# MCU.net
KiCad netlist of a schematic drawn in Altium Designer
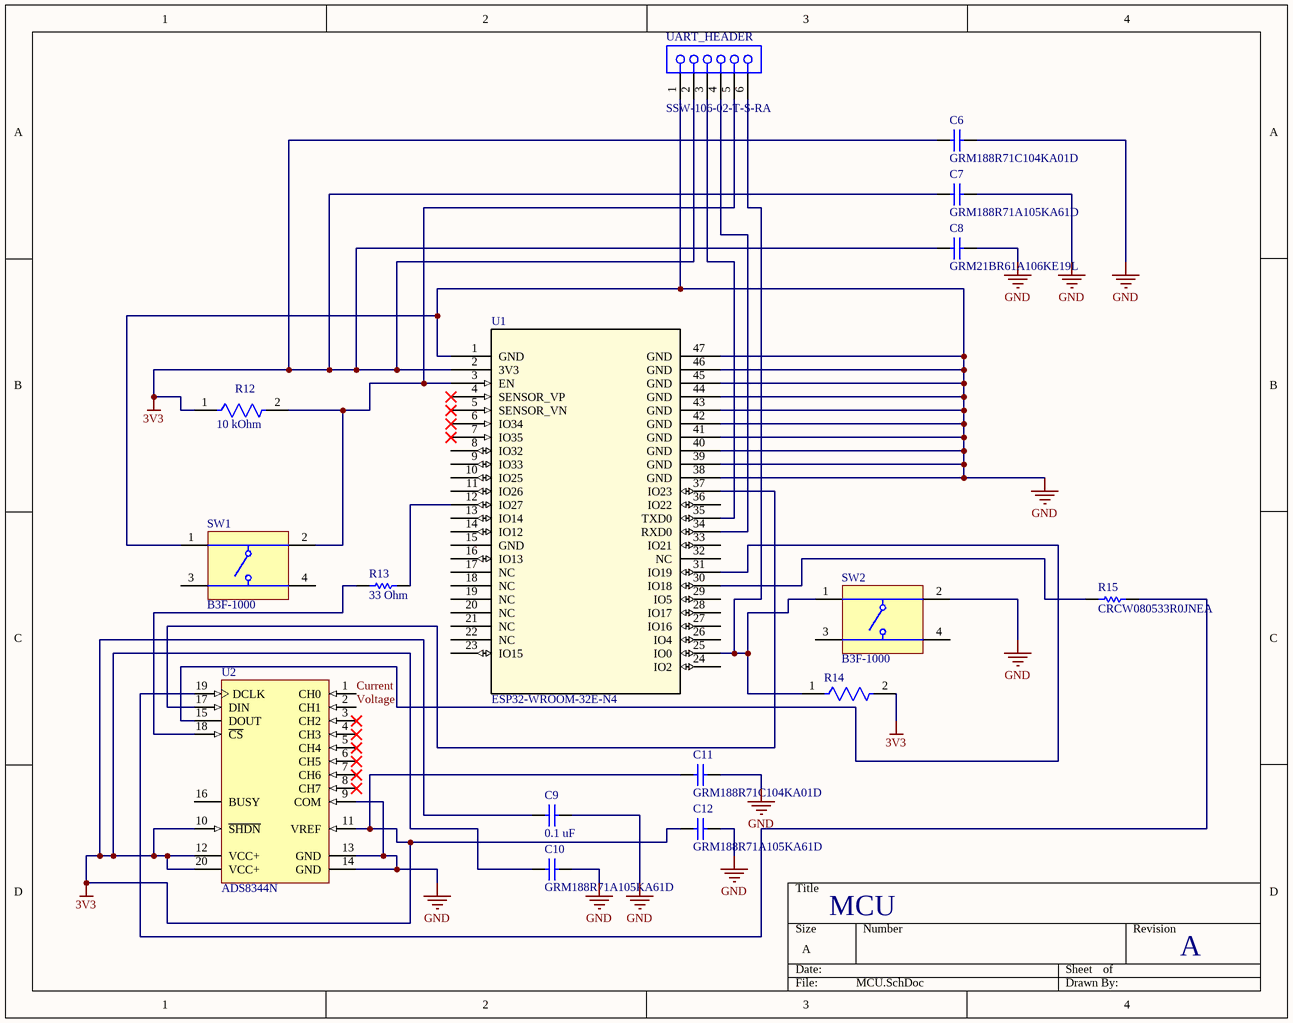
[diagram p0: MCU.SchDoc]

(export (version "E")
  (design (tool "Eeschema 10.0.6"))
  (components
    (comp (ref "C6")
      (value "GRM188R71C104KA01D")
      (footprint "MURA-0603_H_0.9_N")
      (description "CAP, Ceramic, 0.1 uF, 10%, 16 V, 0603, RoHS, Tape and Reel")
      (fields (field (name "MANUFACTURER") "Murata") (field (name "TOLERANCE") "10%"))
      (libsource (lib "Altium Content Vault") (part "CAP-NP-2"))
    )
    (comp (ref "C7")
      (value "GRM188R71A105KA61D")
      (footprint "CAPC1608X90X35ML10T15")
      (fields (field (name "MANUFACTURER") "Murata"))
      (libsource (lib "Altium Content Vault") (part "CAP"))
    )
    (comp (ref "C8")
      (value "GRM21BR61A106KE19L")
      (footprint "MURA-0805_H_1.35_L")
      (description "CAP, Ceramic, 10 uF, 10%, 10 V, 0805, RoHS, Tape and Reel")
      (fields (field (name "MANUFACTURER") "Murata") (field (name "TOLERANCE") "±10%"))
      (libsource (lib "Altium Content Vault") (part "CAP-NP-2"))
    )
    (comp (ref "C9")
      (value "0.1 uF")
      (footprint "MURA-0603_H_0.9_N")
      (description "CAP, Ceramic, 0.1 uF, 10%, 16 V, 0603, RoHS, Tape and Reel")
      (fields (field (name "MANUFACTURER") "Murata") (field (name "TOLERANCE") "10%"))
      (libsource (lib "Altium Content Vault") (part "CAP-NP-2"))
    )
    (comp (ref "C10")
      (value "GRM188R71A105KA61D")
      (footprint "CAPC1608X90X35ML10T15")
      (fields (field (name "MANUFACTURER") "Murata"))
      (libsource (lib "Altium Content Vault") (part "CAP"))
    )
    (comp (ref "C11")
      (value "GRM188R71C104KA01D")
      (footprint "MURA-0603_H_0.9_N")
      (description "CAP, Ceramic, 0.1 uF, 10%, 16 V, 0603, RoHS, Tape and Reel")
      (fields (field (name "MANUFACTURER") "Murata") (field (name "TOLERANCE") "10%"))
      (libsource (lib "Altium Content Vault") (part "CAP-NP-2"))
    )
    (comp (ref "C12")
      (value "GRM188R71A105KA61D")
      (footprint "CAPC1608X90X35ML10T15")
      (fields (field (name "MANUFACTURER") "Murata"))
      (libsource (lib "Altium Content Vault") (part "CAP"))
    )
    (comp (ref "R12")
      (value "10 kOhm")
      (footprint "FP-RC0603-0_55-IPC_B")
      (description "RES 10K OHM 1% 1/10W 0603")
      (fields (field (name "TOLERANCE") "1%"))
      (libsource (lib "Altium Content Vault") (part "1029c3af85768c4190bb7ad29bc67b5"))
    )
    (comp (ref "R13")
      (value "33 Ohm")
      (footprint "RESC2013X50X30ML20T20")
      (fields (field (name "MANUFACTURER") "Vishay Dale") (field (name "PART NUMBER") "CRCW080533R0JNEA"))
      (libsource (lib "Altium Content Vault") (part "RES"))
    )
    (comp (ref "R14")
      (value "RC0603FR-0710KL")
      (footprint "FP-RC0603-0_55-IPC_B")
      (description "RES 10K OHM 1% 1/10W 0603")
      (fields (field (name "TOLERANCE") "1%"))
      (libsource (lib "Altium Content Vault") (part "1029c3af85768c4190bb7ad29bc67b5"))
    )
    (comp (ref "R15")
      (value "CRCW080533R0JNEA")
      (footprint "RESC2013X50X30ML20T20")
      (fields (field (name "MANUFACTURER") "Vishay Dale"))
      (libsource (lib "Altium Content Vault") (part "RES"))
    )
    (comp (ref "SW1")
      (value "B3F-1000")
      (footprint "OMRON-B3F-1000-4_V")
      (description "Tactile Switch, SPST-NO, 0.05 A, 5 to 24 V, -25 to 70 degC, 4-Pin THD, RoHS, Bulk")
      (libsource (lib "Altium Content Vault") (part "SW-SPST-4_A"))
    )
    (comp (ref "SW2")
      (value "B3F-1000")
      (footprint "OMRON-B3F-1000-4_V")
      (description "Tactile Switch, SPST-NO, 0.05 A, 5 to 24 V, -25 to 70 degC, 4-Pin THD, RoHS, Bulk")
      (libsource (lib "Altium Content Vault") (part "SW-SPST-4_A"))
    )
    (comp (ref "U1")
      (value "ESP32-WROOM-32E-N4")
      (footprint "ESP32­WROOM­32E_EXP")
      (description "Description")
      (fields (field (name "COPYRIGHT") "Copyright (C) 2025 Ultra Librarian. All rights reserved."))
      (libsource (lib "ESP32-WROOM-32E-N4") (part "ESP32-WROOM-32E-N4"))
    )
    (comp (ref "U2")
      (value "ADS8344N")
      (footprint "TI-DB20_L")
      (fields (field (name "MANUFACTURER") "Texas Instruments"))
      (libsource (lib "Altium Content Vault") (part "TI-ADS8344DB_DBQ20"))
    )
    (comp (ref "UART_HEADER")
      (value "SSW-106-02-T-S-RA")
      (footprint "SMTC-SSW-106-02-X-S-RA")
      (description "SQ Post Socket, Through-hole, Right Angle, -55 to 105 degC, 2.54mm Pitch, 6-Pin, Female, RoHS")
      (fields (field (name "MANUFACTURER") "Samtec"))
      (libsource (lib "Altium Content Vault") (part "SMTC-SSW-106-02-X-S-X"))
    )
  )
  (nets
    (net (code "1") (name "/Current") (class "Default")
      (node (ref "U2") (pin "1") (pinfunction "CH0_1") (pintype "input"))
    )
    (net (code "2") (name "/Voltage") (class "Default")
      (node (ref "U2") (pin "2") (pinfunction "CH1_2") (pintype "input"))
    )
    (net (code "3") (name "3V3") (class "Default")
      (node (ref "C10") (pin "1") (pinfunction "1_1") (pintype "passive"))
      (node (ref "C11") (pin "1") (pinfunction "1_1") (pintype "passive"))
      (node (ref "C12") (pin "1") (pinfunction "1_1") (pintype "passive"))
      (node (ref "C6") (pin "1") (pinfunction "1_1") (pintype "passive"))
      (node (ref "C7") (pin "1") (pinfunction "1_1") (pintype "passive"))
      (node (ref "C8") (pin "1") (pinfunction "1_1") (pintype "passive"))
      (node (ref "C9") (pin "1") (pinfunction "1_1") (pintype "passive"))
      (node (ref "R12") (pin "1") (pinfunction "1_1") (pintype "passive"))
      (node (ref "R14") (pin "2") (pinfunction "2_2") (pintype "passive"))
      (node (ref "U1") (pin "2") (pinfunction "3V3_2") (pintype "power_in"))
      (node (ref "U2") (pin "10") (pinfunction "~{SHDN}_10") (pintype "input"))
      (node (ref "U2") (pin "11") (pinfunction "VREF_11") (pintype "input"))
      (node (ref "U2") (pin "12") (pinfunction "VCC+_12") (pintype "power_in"))
      (node (ref "U2") (pin "20") (pinfunction "VCC+_20") (pintype "power_in"))
      (node (ref "UART_HEADER") (pin "2") (pinfunction "2_2") (pintype "passive"))
    )
    (net (code "4") (name "GND") (class "Default")
      (node (ref "C10") (pin "2") (pinfunction "2_2") (pintype "passive"))
      (node (ref "C11") (pin "2") (pinfunction "2_2") (pintype "passive"))
      (node (ref "C12") (pin "2") (pinfunction "2_2") (pintype "passive"))
      (node (ref "C6") (pin "2") (pinfunction "2_2") (pintype "passive"))
      (node (ref "C7") (pin "2") (pinfunction "2_2") (pintype "passive"))
      (node (ref "C8") (pin "2") (pinfunction "2_2") (pintype "passive"))
      (node (ref "C9") (pin "2") (pinfunction "2_2") (pintype "passive"))
      (node (ref "SW1") (pin "1") (pinfunction "1_1") (pintype "passive"))
      (node (ref "SW2") (pin "2") (pinfunction "2_2") (pintype "passive"))
      (node (ref "U1") (pin "1") (pinfunction "GND_1") (pintype "power_in"))
      (node (ref "U1") (pin "38") (pinfunction "GND_38") (pintype "power_in"))
      (node (ref "U1") (pin "39") (pinfunction "GND_39") (pintype "power_in"))
      (node (ref "U1") (pin "40") (pinfunction "GND_40") (pintype "power_in"))
      (node (ref "U1") (pin "41") (pinfunction "GND_41") (pintype "power_in"))
      (node (ref "U1") (pin "42") (pinfunction "GND_42") (pintype "power_in"))
      (node (ref "U1") (pin "43") (pinfunction "GND_43") (pintype "power_in"))
      (node (ref "U1") (pin "44") (pinfunction "GND_44") (pintype "power_in"))
      (node (ref "U1") (pin "45") (pinfunction "GND_45") (pintype "power_in"))
      (node (ref "U1") (pin "46") (pinfunction "GND_46") (pintype "power_in"))
      (node (ref "U1") (pin "47") (pinfunction "GND_47") (pintype "power_in"))
      (node (ref "U2") (pin "13") (pinfunction "GND_13") (pintype "power_in"))
      (node (ref "U2") (pin "14") (pinfunction "GND_14") (pintype "power_in"))
      (node (ref "U2") (pin "9") (pinfunction "COM_9") (pintype "input"))
      (node (ref "UART_HEADER") (pin "1") (pinfunction "1_1") (pintype "passive"))
    )
    (net (code "5") (name "Net-(U1-EN)") (class "Default")
      (node (ref "R12") (pin "2") (pinfunction "2_2") (pintype "passive"))
      (node (ref "SW1") (pin "2") (pinfunction "2_2") (pintype "passive"))
      (node (ref "U1") (pin "3") (pinfunction "EN_3") (pintype "input"))
      (node (ref "UART_HEADER") (pin "5") (pinfunction "5_5") (pintype "passive"))
    )
    (net (code "6") (name "Net-(U1-IO0)") (class "Default")
      (node (ref "R14") (pin "1") (pinfunction "1_1") (pintype "passive"))
      (node (ref "SW2") (pin "1") (pinfunction "1_1") (pintype "passive"))
      (node (ref "U1") (pin "25") (pinfunction "IO0_25") (pintype "bidirectional"))
      (node (ref "UART_HEADER") (pin "6") (pinfunction "6_6") (pintype "passive"))
    )
    (net (code "7") (name "Net-(U1-IO18)") (class "Default")
      (node (ref "R15") (pin "1") (pinfunction "1_1") (pintype "passive"))
      (node (ref "U1") (pin "30") (pinfunction "IO18_30") (pintype "bidirectional"))
    )
    (net (code "8") (name "Net-(U1-IO19)") (class "Default")
      (node (ref "U1") (pin "31") (pinfunction "IO19_31") (pintype "bidirectional"))
      (node (ref "U2") (pin "15") (pinfunction "DOUT_15") (pintype "tri_state"))
    )
    (net (code "9") (name "Net-(U1-IO23)") (class "Default")
      (node (ref "U1") (pin "37") (pinfunction "IO23_37") (pintype "bidirectional"))
      (node (ref "U2") (pin "17") (pinfunction "DIN_17") (pintype "input"))
    )
    (net (code "10") (name "Net-(U1-IO27)") (class "Default")
      (node (ref "R13") (pin "2") (pinfunction "2_2") (pintype "passive"))
      (node (ref "U1") (pin "12") (pinfunction "IO27_12") (pintype "bidirectional"))
    )
    (net (code "11") (name "Net-(U1-RXD0)") (class "Default")
      (node (ref "U1") (pin "34") (pinfunction "RXD0_34") (pintype "bidirectional"))
      (node (ref "UART_HEADER") (pin "4") (pinfunction "4_4") (pintype "passive"))
    )
    (net (code "12") (name "Net-(U1-TXD0)") (class "Default")
      (node (ref "U1") (pin "35") (pinfunction "TXD0_35") (pintype "bidirectional"))
      (node (ref "UART_HEADER") (pin "3") (pinfunction "3_3") (pintype "passive"))
    )
    (net (code "13") (name "Net-(U2-DCLK)") (class "Default")
      (node (ref "R15") (pin "2") (pinfunction "2_2") (pintype "passive"))
      (node (ref "U2") (pin "19") (pinfunction "DCLK_19") (pintype "input"))
    )
    (net (code "14") (name "Net-(U2-~{CS})") (class "Default")
      (node (ref "R13") (pin "1") (pinfunction "1_1") (pintype "passive"))
      (node (ref "U2") (pin "18") (pinfunction "~{CS}_18") (pintype "input"))
    )
    (net (code "15") (name "unconnected-(SW1-Pad3)") (class "Default")
      (node (ref "SW1") (pin "3") (pinfunction "3_3") (pintype "passive"))
    )
    (net (code "16") (name "unconnected-(SW1-Pad4)") (class "Default")
      (node (ref "SW1") (pin "4") (pinfunction "4_4") (pintype "passive"))
    )
    (net (code "17") (name "unconnected-(SW2-Pad3)") (class "Default")
      (node (ref "SW2") (pin "3") (pinfunction "3_3") (pintype "passive"))
    )
    (net (code "18") (name "unconnected-(SW2-Pad4)") (class "Default")
      (node (ref "SW2") (pin "4") (pinfunction "4_4") (pintype "passive"))
    )
    (net (code "19") (name "unconnected-(U1-GND-Pad15)") (class "Default")
      (node (ref "U1") (pin "15") (pinfunction "GND_15") (pintype "power_in"))
    )
    (net (code "20") (name "unconnected-(U1-IO2-Pad24)") (class "Default")
      (node (ref "U1") (pin "24") (pinfunction "IO2_24") (pintype "bidirectional"))
    )
    (net (code "21") (name "unconnected-(U1-IO4-Pad26)") (class "Default")
      (node (ref "U1") (pin "26") (pinfunction "IO4_26") (pintype "bidirectional"))
    )
    (net (code "22") (name "unconnected-(U1-IO5-Pad29)") (class "Default")
      (node (ref "U1") (pin "29") (pinfunction "IO5_29") (pintype "bidirectional"))
    )
    (net (code "23") (name "unconnected-(U1-IO12-Pad14)") (class "Default")
      (node (ref "U1") (pin "14") (pinfunction "IO12_14") (pintype "bidirectional"))
    )
    (net (code "24") (name "unconnected-(U1-IO13-Pad16)") (class "Default")
      (node (ref "U1") (pin "16") (pinfunction "IO13_16") (pintype "bidirectional"))
    )
    (net (code "25") (name "unconnected-(U1-IO14-Pad13)") (class "Default")
      (node (ref "U1") (pin "13") (pinfunction "IO14_13") (pintype "bidirectional"))
    )
    (net (code "26") (name "unconnected-(U1-IO15-Pad23)") (class "Default")
      (node (ref "U1") (pin "23") (pinfunction "IO15_23") (pintype "bidirectional"))
    )
    (net (code "27") (name "unconnected-(U1-IO16-Pad27)") (class "Default")
      (node (ref "U1") (pin "27") (pinfunction "IO16_27") (pintype "bidirectional"))
    )
    (net (code "28") (name "unconnected-(U1-IO17-Pad28)") (class "Default")
      (node (ref "U1") (pin "28") (pinfunction "IO17_28") (pintype "bidirectional"))
    )
    (net (code "29") (name "unconnected-(U1-IO21-Pad33)") (class "Default")
      (node (ref "U1") (pin "33") (pinfunction "IO21_33") (pintype "bidirectional"))
    )
    (net (code "30") (name "unconnected-(U1-IO22-Pad36)") (class "Default")
      (node (ref "U1") (pin "36") (pinfunction "IO22_36") (pintype "bidirectional"))
    )
    (net (code "31") (name "unconnected-(U1-IO25-Pad10)") (class "Default")
      (node (ref "U1") (pin "10") (pinfunction "IO25_10") (pintype "bidirectional"))
    )
    (net (code "32") (name "unconnected-(U1-IO26-Pad11)") (class "Default")
      (node (ref "U1") (pin "11") (pinfunction "IO26_11") (pintype "bidirectional"))
    )
    (net (code "33") (name "unconnected-(U1-IO32-Pad8)") (class "Default")
      (node (ref "U1") (pin "8") (pinfunction "IO32_8") (pintype "bidirectional"))
    )
    (net (code "34") (name "unconnected-(U1-IO33-Pad9)") (class "Default")
      (node (ref "U1") (pin "9") (pinfunction "IO33_9") (pintype "bidirectional"))
    )
    (net (code "35") (name "unconnected-(U1-IO34-Pad6)") (class "Default")
      (node (ref "U1") (pin "6") (pinfunction "IO34_6") (pintype "input+no_connect"))
    )
    (net (code "36") (name "unconnected-(U1-IO35-Pad7)") (class "Default")
      (node (ref "U1") (pin "7") (pinfunction "IO35_7") (pintype "input+no_connect"))
    )
    (net (code "37") (name "unconnected-(U1-NC-Pad17)") (class "Default")
      (node (ref "U1") (pin "17") (pinfunction "NC_17") (pintype "passive"))
    )
    (net (code "38") (name "unconnected-(U1-NC-Pad18)") (class "Default")
      (node (ref "U1") (pin "18") (pinfunction "NC_18") (pintype "passive"))
    )
    (net (code "39") (name "unconnected-(U1-NC-Pad19)") (class "Default")
      (node (ref "U1") (pin "19") (pinfunction "NC_19") (pintype "passive"))
    )
    (net (code "40") (name "unconnected-(U1-NC-Pad20)") (class "Default")
      (node (ref "U1") (pin "20") (pinfunction "NC_20") (pintype "passive"))
    )
    (net (code "41") (name "unconnected-(U1-NC-Pad21)") (class "Default")
      (node (ref "U1") (pin "21") (pinfunction "NC_21") (pintype "passive"))
    )
    (net (code "42") (name "unconnected-(U1-NC-Pad22)") (class "Default")
      (node (ref "U1") (pin "22") (pinfunction "NC_22") (pintype "passive"))
    )
    (net (code "43") (name "unconnected-(U1-NC-Pad32)") (class "Default")
      (node (ref "U1") (pin "32") (pinfunction "NC_32") (pintype "passive"))
    )
    (net (code "44") (name "unconnected-(U1-SENSOR_VN-Pad5)") (class "Default")
      (node (ref "U1") (pin "5") (pinfunction "SENSOR_VN_5") (pintype "input+no_connect"))
    )
    (net (code "45") (name "unconnected-(U1-SENSOR_VP-Pad4)") (class "Default")
      (node (ref "U1") (pin "4") (pinfunction "SENSOR_VP_4") (pintype "input+no_connect"))
    )
    (net (code "46") (name "unconnected-(U2-BUSY-Pad16)") (class "Default")
      (node (ref "U2") (pin "16") (pinfunction "BUSY_16") (pintype "tri_state"))
    )
    (net (code "47") (name "unconnected-(U2-CH2-Pad3)") (class "Default")
      (node (ref "U2") (pin "3") (pinfunction "CH2_3") (pintype "input+no_connect"))
    )
    (net (code "48") (name "unconnected-(U2-CH3-Pad4)") (class "Default")
      (node (ref "U2") (pin "4") (pinfunction "CH3_4") (pintype "input+no_connect"))
    )
    (net (code "49") (name "unconnected-(U2-CH4-Pad5)") (class "Default")
      (node (ref "U2") (pin "5") (pinfunction "CH4_5") (pintype "input+no_connect"))
    )
    (net (code "50") (name "unconnected-(U2-CH5-Pad6)") (class "Default")
      (node (ref "U2") (pin "6") (pinfunction "CH5_6") (pintype "input+no_connect"))
    )
    (net (code "51") (name "unconnected-(U2-CH6-Pad7)") (class "Default")
      (node (ref "U2") (pin "7") (pinfunction "CH6_7") (pintype "input+no_connect"))
    )
    (net (code "52") (name "unconnected-(U2-CH7-Pad8)") (class "Default")
      (node (ref "U2") (pin "8") (pinfunction "CH7_8") (pintype "input+no_connect"))
    )
  )
)
